# sim-breakout.net
KiCad netlist of a schematic drawn in EAGLE
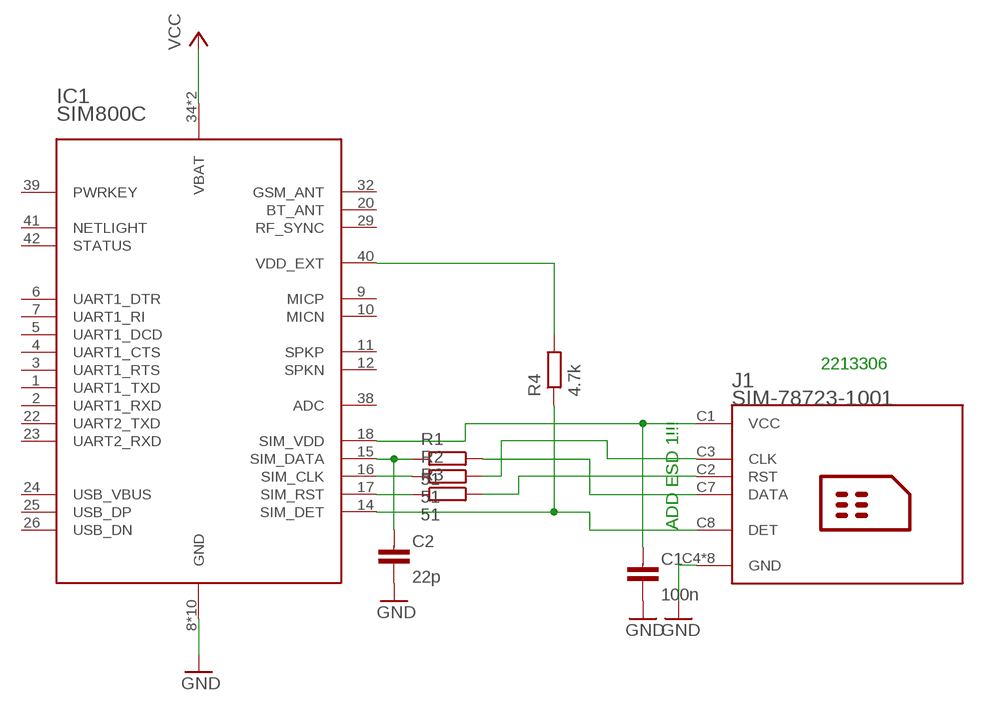
[diagram p0: schematic, sheet 1]

(export (version "E")
  (design (tool "Eeschema 10.0.6"))
  (components
    (comp (ref "C1")
      (value "100n")
      (footprint "eagle-import:C0603-N")
      (libsource (lib "eagle-import") (part "CAPACITOR0603-N"))
    )
    (comp (ref "C2")
      (value "22p")
      (footprint "eagle-import:C0603-N")
      (libsource (lib "eagle-import") (part "CAPACITOR0603-N"))
    )
    (comp (ref "IC1")
      (value "SIM800C")
      (footprint "eagle-import:SIM800C")
      (libsource (lib "eagle-import") (part "SIM800C"))
    )
    (comp (ref "J1")
      (value "SIM-78723-1001")
      (footprint "eagle-import:MSIM-MOLEX")
      (libsource (lib "eagle-import") (part "SIM-78723-1001"))
    )
    (comp (ref "R1")
      (value "51")
      (footprint "eagle-import:R0603-N")
      (libsource (lib "eagle-import") (part "RESISTOR0603-N"))
    )
    (comp (ref "R2")
      (value "51")
      (footprint "eagle-import:R0603-N")
      (libsource (lib "eagle-import") (part "RESISTOR0603-N"))
    )
    (comp (ref "R3")
      (value "51")
      (footprint "eagle-import:R0603-N")
      (libsource (lib "eagle-import") (part "RESISTOR0603-N"))
    )
    (comp (ref "R4")
      (value "4.7k")
      (footprint "eagle-import:R0603-N")
      (libsource (lib "eagle-import") (part "RESISTOR0603-N"))
    )
  )
  (nets
    (net (code "1") (name "/USB_VBUS") (class "Default")
      (node (ref "IC1") (pin "24") (pinfunction "USB_VBUS_24") (pintype "power_in"))
    )
    (net (code "2") (name "GND") (class "Default")
      (node (ref "C1") (pin "2") (pinfunction "2_2") (pintype "passive"))
      (node (ref "C2") (pin "2") (pinfunction "2_2") (pintype "passive"))
      (node (ref "IC1") (pin "13") (pinfunction "GND_13") (pintype "power_in"))
      (node (ref "IC1") (pin "19") (pinfunction "GND_19") (pintype "power_in"))
      (node (ref "IC1") (pin "21") (pinfunction "GND_21") (pintype "power_in"))
      (node (ref "IC1") (pin "27") (pinfunction "GND_27") (pintype "power_in"))
      (node (ref "IC1") (pin "30") (pinfunction "GND_30") (pintype "power_in"))
      (node (ref "IC1") (pin "31") (pinfunction "GND_31") (pintype "power_in"))
      (node (ref "IC1") (pin "33") (pinfunction "GND_33") (pintype "power_in"))
      (node (ref "IC1") (pin "36") (pinfunction "GND_36") (pintype "power_in"))
      (node (ref "IC1") (pin "37") (pinfunction "GND_37") (pintype "power_in"))
      (node (ref "IC1") (pin "8") (pinfunction "GND_8") (pintype "power_in"))
      (node (ref "J1") (pin "C4") (pinfunction "GND_C4") (pintype "power_in"))
      (node (ref "J1") (pin "C5") (pinfunction "GND_C5") (pintype "power_in"))
      (node (ref "J1") (pin "GND1") (pinfunction "GND_GND1") (pintype "power_in"))
      (node (ref "J1") (pin "GND2") (pinfunction "GND_GND2") (pintype "power_in"))
      (node (ref "J1") (pin "GND3") (pinfunction "GND_GND3") (pintype "power_in"))
      (node (ref "J1") (pin "GND4") (pinfunction "GND_GND4") (pintype "power_in"))
      (node (ref "J1") (pin "GND5") (pinfunction "GND_GND5") (pintype "power_in"))
      (node (ref "J1") (pin "GND6") (pinfunction "GND_GND6") (pintype "power_in"))
    )
    (net (code "3") (name "Net-(IC1-SIM_CLK)") (class "Default")
      (node (ref "IC1") (pin "16") (pinfunction "SIM_CLK_16") (pintype "output"))
      (node (ref "R2") (pin "1") (pinfunction "P$1_1") (pintype "passive"))
    )
    (net (code "4") (name "Net-(IC1-SIM_DATA)") (class "Default")
      (node (ref "C2") (pin "1") (pinfunction "1_1") (pintype "passive"))
      (node (ref "IC1") (pin "15") (pinfunction "SIM_DATA_15") (pintype "bidirectional"))
      (node (ref "R1") (pin "1") (pinfunction "P$1_1") (pintype "passive"))
    )
    (net (code "5") (name "Net-(IC1-SIM_DET)") (class "Default")
      (node (ref "IC1") (pin "14") (pinfunction "SIM_DET_14") (pintype "input"))
      (node (ref "J1") (pin "C8") (pinfunction "DET_C8") (pintype "output"))
      (node (ref "R4") (pin "1") (pinfunction "P$1_1") (pintype "passive"))
    )
    (net (code "6") (name "Net-(IC1-SIM_RST)") (class "Default")
      (node (ref "IC1") (pin "17") (pinfunction "SIM_RST_17") (pintype "output"))
      (node (ref "R3") (pin "1") (pinfunction "P$1_1") (pintype "passive"))
    )
    (net (code "7") (name "Net-(IC1-SIM_VDD)") (class "Default")
      (node (ref "C1") (pin "1") (pinfunction "1_1") (pintype "passive"))
      (node (ref "IC1") (pin "18") (pinfunction "SIM_VDD_18") (pintype "power_in"))
      (node (ref "J1") (pin "C1") (pinfunction "VCC_C1") (pintype "power_in"))
    )
    (net (code "8") (name "Net-(IC1-VDD_EXT)") (class "Default")
      (node (ref "IC1") (pin "40") (pinfunction "VDD_EXT_40") (pintype "power_in"))
      (node (ref "R4") (pin "2") (pinfunction "P$2_2") (pintype "passive"))
    )
    (net (code "9") (name "Net-(J1-CLK)") (class "Default")
      (node (ref "J1") (pin "C3") (pinfunction "CLK_C3") (pintype "input"))
      (node (ref "R2") (pin "2") (pinfunction "P$2_2") (pintype "passive"))
    )
    (net (code "10") (name "Net-(J1-DATA)") (class "Default")
      (node (ref "J1") (pin "C7") (pinfunction "DATA_C7") (pintype "bidirectional"))
      (node (ref "R1") (pin "2") (pinfunction "P$2_2") (pintype "passive"))
    )
    (net (code "11") (name "Net-(J1-RST)") (class "Default")
      (node (ref "J1") (pin "C2") (pinfunction "RST_C2") (pintype "input"))
      (node (ref "R3") (pin "2") (pinfunction "P$2_2") (pintype "passive"))
    )
    (net (code "12") (name "VCC") (class "Default")
      (node (ref "IC1") (pin "34") (pinfunction "VBAT_34") (pintype "power_in"))
      (node (ref "IC1") (pin "35") (pinfunction "VBAT_35") (pintype "power_in"))
    )
    (net (code "13") (name "unconnected-(IC1-ADC-Pad38)") (class "Default")
      (node (ref "IC1") (pin "38") (pinfunction "ADC_38") (pintype "input"))
    )
    (net (code "14") (name "unconnected-(IC1-BT_ANT-Pad20)") (class "Default")
      (node (ref "IC1") (pin "20") (pinfunction "BT_ANT_20") (pintype "bidirectional"))
    )
    (net (code "15") (name "unconnected-(IC1-GSM_ANT-Pad32)") (class "Default")
      (node (ref "IC1") (pin "32") (pinfunction "GSM_ANT_32") (pintype "bidirectional"))
    )
    (net (code "16") (name "unconnected-(IC1-MICN-Pad10)") (class "Default")
      (node (ref "IC1") (pin "10") (pinfunction "MICN_10") (pintype "input"))
    )
    (net (code "17") (name "unconnected-(IC1-MICP-Pad9)") (class "Default")
      (node (ref "IC1") (pin "9") (pinfunction "MICP_9") (pintype "input"))
    )
    (net (code "18") (name "unconnected-(IC1-NETLIGHT-Pad41)") (class "Default")
      (node (ref "IC1") (pin "41") (pinfunction "NETLIGHT_41") (pintype "output"))
    )
    (net (code "19") (name "unconnected-(IC1-PWRKEY-Pad39)") (class "Default")
      (node (ref "IC1") (pin "39") (pinfunction "PWRKEY_39") (pintype "input"))
    )
    (net (code "20") (name "unconnected-(IC1-RF_SYNC-Pad29)") (class "Default")
      (node (ref "IC1") (pin "29") (pinfunction "RF_SYNC_29") (pintype "output"))
    )
    (net (code "21") (name "unconnected-(IC1-SPKN-Pad12)") (class "Default")
      (node (ref "IC1") (pin "12") (pinfunction "SPKN_12") (pintype "output"))
    )
    (net (code "22") (name "unconnected-(IC1-SPKP-Pad11)") (class "Default")
      (node (ref "IC1") (pin "11") (pinfunction "SPKP_11") (pintype "output"))
    )
    (net (code "23") (name "unconnected-(IC1-STATUS-Pad42)") (class "Default")
      (node (ref "IC1") (pin "42") (pinfunction "STATUS_42") (pintype "output"))
    )
    (net (code "24") (name "unconnected-(IC1-UART1_CTS-Pad4)") (class "Default")
      (node (ref "IC1") (pin "4") (pinfunction "UART1_CTS_4") (pintype "output"))
    )
    (net (code "25") (name "unconnected-(IC1-UART1_DCD-Pad5)") (class "Default")
      (node (ref "IC1") (pin "5") (pinfunction "UART1_DCD_5") (pintype "output"))
    )
    (net (code "26") (name "unconnected-(IC1-UART1_DTR-Pad6)") (class "Default")
      (node (ref "IC1") (pin "6") (pinfunction "UART1_DTR_6") (pintype "input"))
    )
    (net (code "27") (name "unconnected-(IC1-UART1_RI-Pad7)") (class "Default")
      (node (ref "IC1") (pin "7") (pinfunction "UART1_RI_7") (pintype "output"))
    )
    (net (code "28") (name "unconnected-(IC1-UART1_RTS-Pad3)") (class "Default")
      (node (ref "IC1") (pin "3") (pinfunction "UART1_RTS_3") (pintype "input"))
    )
    (net (code "29") (name "unconnected-(IC1-UART1_RXD-Pad2)") (class "Default")
      (node (ref "IC1") (pin "2") (pinfunction "UART1_RXD_2") (pintype "output"))
    )
    (net (code "30") (name "unconnected-(IC1-UART1_TXD-Pad1)") (class "Default")
      (node (ref "IC1") (pin "1") (pinfunction "UART1_TXD_1") (pintype "output"))
    )
    (net (code "31") (name "unconnected-(IC1-UART2_RXD-Pad23)") (class "Default")
      (node (ref "IC1") (pin "23") (pinfunction "UART2_RXD_23") (pintype "output"))
    )
    (net (code "32") (name "unconnected-(IC1-UART2_TXD-Pad22)") (class "Default")
      (node (ref "IC1") (pin "22") (pinfunction "UART2_TXD_22") (pintype "output"))
    )
    (net (code "33") (name "unconnected-(IC1-USB_DN-Pad26)") (class "Default")
      (node (ref "IC1") (pin "26") (pinfunction "USB_DN_26") (pintype "output"))
    )
    (net (code "34") (name "unconnected-(IC1-USB_DP-Pad25)") (class "Default")
      (node (ref "IC1") (pin "25") (pinfunction "USB_DP_25") (pintype "bidirectional"))
    )
  )
)
